# misc.net
KiCad netlist of a schematic drawn in Altium Designer
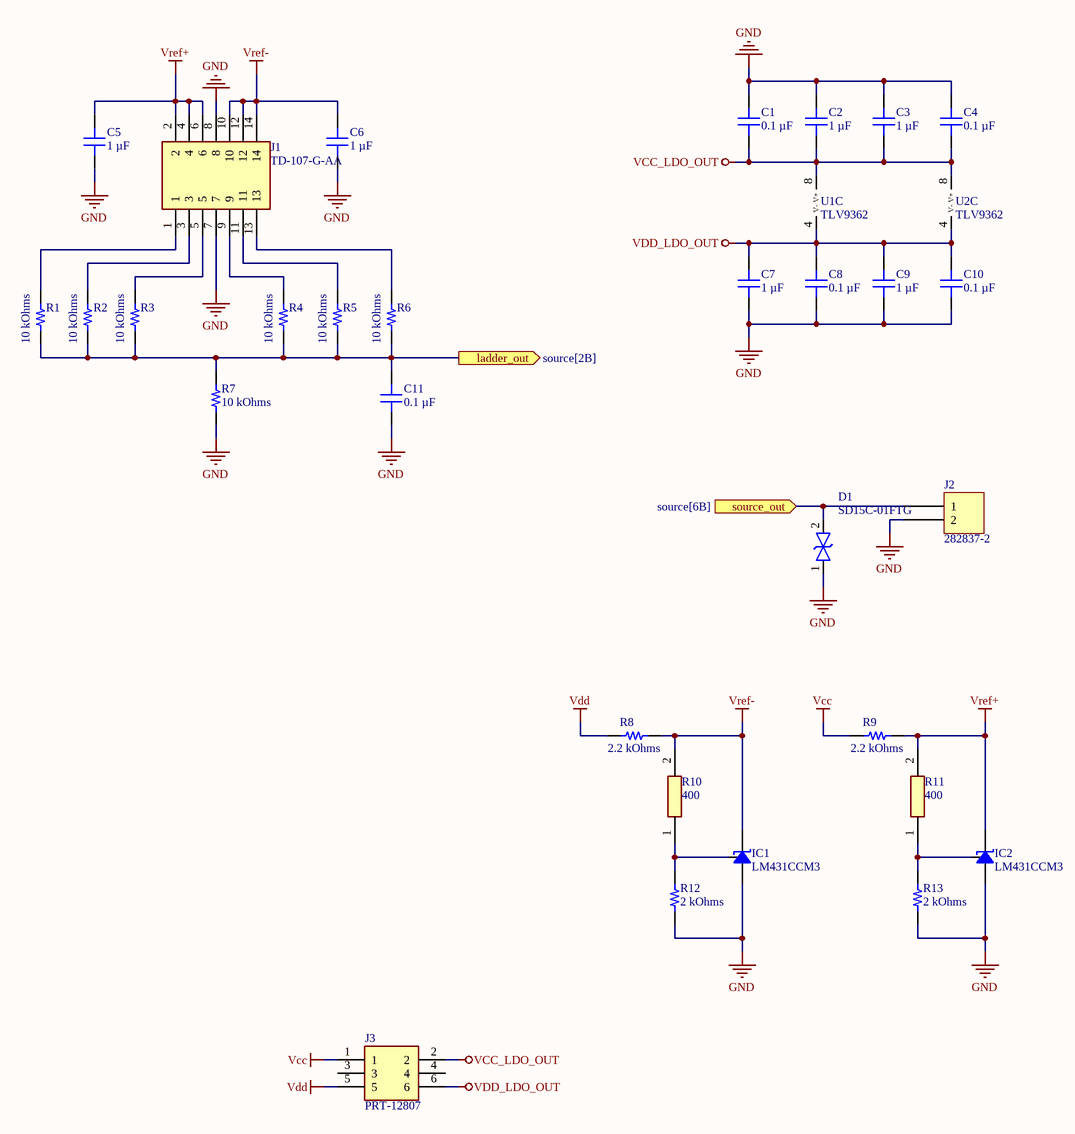
[diagram p0: misc.SchDoc]

(export (version "E")
  (design (tool "Eeschema 10.0.6"))
  (components
    (comp (ref "C1")
      (value "0.1 µF")
      (footprint "CAP 1206_3216 - 0.8MM")
      (description "CAP CER 0.1UF 50V X7R 1206")
      (fields
        (field (name "PART NUMBER") "885012208087")
        (field (name "CAPACITANCE") "0.1 µF")
        (field (name "MANUFACTURER") "Würth Elektronik")
      )
      (libsource (lib "Celestial Altium Library - altium_library") (part "Capacitor"))
    )
    (comp (ref "C2")
      (value "1 µF")
      (footprint "CAP 1206_3216 - 0.8MM")
      (description "CAP CER 1UF 50V X7R 1206")
      (fields
        (field (name "PART NUMBER") "885012208093")
        (field (name "CAPACITANCE") "1 µF")
        (field (name "MANUFACTURER") "Würth Elektronik")
      )
      (libsource (lib "Celestial Altium Library - altium_library") (part "Capacitor"))
    )
    (comp (ref "C3")
      (value "1 µF")
      (footprint "CAP 1206_3216 - 0.8MM")
      (description "CAP CER 1UF 50V X7R 1206")
      (fields
        (field (name "PART NUMBER") "885012208093")
        (field (name "CAPACITANCE") "1 µF")
        (field (name "MANUFACTURER") "Würth Elektronik")
      )
      (libsource (lib "Celestial Altium Library - altium_library") (part "Capacitor"))
    )
    (comp (ref "C4")
      (value "0.1 µF")
      (footprint "CAP 1206_3216 - 0.8MM")
      (description "CAP CER 0.1UF 50V X7R 1206")
      (fields
        (field (name "PART NUMBER") "885012208087")
        (field (name "CAPACITANCE") "0.1 µF")
        (field (name "MANUFACTURER") "Würth Elektronik")
      )
      (libsource (lib "Celestial Altium Library - altium_library") (part "Capacitor"))
    )
    (comp (ref "C5")
      (value "1 µF")
      (footprint "CAP 1206_3216 - 0.8MM")
      (description "CAP CER 1UF 50V X7R 1206")
      (fields
        (field (name "PART NUMBER") "885012208093")
        (field (name "CAPACITANCE") "1 µF")
        (field (name "MANUFACTURER") "Würth Elektronik")
      )
      (libsource (lib "Celestial Altium Library - altium_library") (part "Capacitor"))
    )
    (comp (ref "C6")
      (value "1 µF")
      (footprint "CAP 1206_3216 - 0.8MM")
      (description "CAP CER 1UF 50V X7R 1206")
      (fields
        (field (name "PART NUMBER") "885012208093")
        (field (name "CAPACITANCE") "1 µF")
        (field (name "MANUFACTURER") "Würth Elektronik")
      )
      (libsource (lib "Celestial Altium Library - altium_library") (part "Capacitor"))
    )
    (comp (ref "C7")
      (value "1 µF")
      (footprint "CAP 1206_3216 - 0.8MM")
      (description "CAP CER 1UF 50V X7R 1206")
      (fields
        (field (name "PART NUMBER") "885012208093")
        (field (name "CAPACITANCE") "1 µF")
        (field (name "MANUFACTURER") "Würth Elektronik")
      )
      (libsource (lib "Celestial Altium Library - altium_library") (part "Capacitor"))
    )
    (comp (ref "C8")
      (value "0.1 µF")
      (footprint "CAP 1206_3216 - 0.8MM")
      (description "CAP CER 0.1UF 50V X7R 1206")
      (fields
        (field (name "PART NUMBER") "885012208087")
        (field (name "CAPACITANCE") "0.1 µF")
        (field (name "MANUFACTURER") "Würth Elektronik")
      )
      (libsource (lib "Celestial Altium Library - altium_library") (part "Capacitor"))
    )
    (comp (ref "C9")
      (value "1 µF")
      (footprint "CAP 1206_3216 - 0.8MM")
      (description "CAP CER 1UF 50V X7R 1206")
      (fields
        (field (name "PART NUMBER") "885012208093")
        (field (name "CAPACITANCE") "1 µF")
        (field (name "MANUFACTURER") "Würth Elektronik")
      )
      (libsource (lib "Celestial Altium Library - altium_library") (part "Capacitor"))
    )
    (comp (ref "C10")
      (value "0.1 µF")
      (footprint "CAP 1206_3216 - 0.8MM")
      (description "CAP CER 0.1UF 50V X7R 1206")
      (fields
        (field (name "PART NUMBER") "885012208087")
        (field (name "CAPACITANCE") "0.1 µF")
        (field (name "MANUFACTURER") "Würth Elektronik")
      )
      (libsource (lib "Celestial Altium Library - altium_library") (part "Capacitor"))
    )
    (comp (ref "C11")
      (value "0.1 µF")
      (footprint "CAP 1206_3216 - 0.8MM")
      (description "CAP CER 0.1UF 50V X7R 1206")
      (fields
        (field (name "PART NUMBER") "885012208087")
        (field (name "CAPACITANCE") "0.1 µF")
        (field (name "MANUFACTURER") "Würth Elektronik")
      )
      (libsource (lib "Celestial Altium Library - altium_library") (part "Capacitor"))
    )
    (comp (ref "D1")
      (value "SD15C-01FTG")
      (footprint "za_koncar:SD15C01FTG")
      (description "TVS Diode (Bi-directional)")
      (fields (field (name "MOUSER PART NUMBER") "576-SD15C-01FTG"))
      (libsource (lib "za_koncar") (part "SD15C-01FTG"))
    )
    (comp (ref "IC1")
      (value "LM431CCM3")
      (footprint "SOT96P240X110-3N")
      (description "Integrated Circuit")
      (fields
        (field (name "MANUFACTURER_PART_NUMBER") "LM431CCM3/NOPB")
        (field (name "MOUSER PART NUMBER") "926-LM431CCM3/NOPB")
      )
      (libsource (lib "za_koncar") (part "LM431CCM3_NOPB"))
    )
    (comp (ref "IC2")
      (value "LM431CCM3")
      (footprint "SOT96P240X110-3N")
      (description "Integrated Circuit")
      (fields
        (field (name "MANUFACTURER_PART_NUMBER") "LM431CCM3/NOPB")
        (field (name "MOUSER PART NUMBER") "926-LM431CCM3/NOPB")
      )
      (libsource (lib "za_koncar") (part "LM431CCM3_NOPB"))
    )
    (comp (ref "J1")
      (value "TD-107-G-AA")
      (footprint "HDRV14W46P254_2X7_1778X508X818P")
      (description "Connector")
      (fields (field (name "MOUSER PART NUMBER") "200-TD107GAA"))
      (libsource (lib "za_koncar") (part "TD-107-G-AA"))
    )
    (comp (ref "J2")
      (value "282837-2")
      (footprint "TE 282837-2")
      (description "TERM BLK 2P SIDE ENT 5.08MM PCB")
      (fields (field (name "MANUFACTURER") "TE Connectivity AMP Connectors") (field (name "VOLTAGE") "300 V"))
      (libsource (lib "Celestial Altium Library - altium_library") (part "2 Pin"))
    )
    (comp (ref "J3")
      (value "PRT-12807")
      (footprint "HDRV6W82P254_2X3_762X500X884P")
      (description "Connector")
      (fields (field (name "MOUSER PART NUMBER") "474-PRT-12807"))
      (libsource (lib "za_koncar") (part "PRT-12807"))
    )
    (comp (ref "R1")
      (value "10 kOhms")
      (footprint "YAGEO RES 1206_3216")
      (description "RES SMD 10K OHM 1% 1/4W 1206")
      (fields (field (name "PART NUMBER") "RT1206FRE0710KL") (field (name "MANUFACTURER") "Yageo"))
      (libsource (lib "Celestial Altium Library - altium_library") (part "Resistor"))
    )
    (comp (ref "R2")
      (value "10 kOhms")
      (footprint "YAGEO RES 1206_3216")
      (description "RES SMD 10K OHM 1% 1/4W 1206")
      (fields (field (name "PART NUMBER") "RT1206FRE0710KL") (field (name "MANUFACTURER") "Yageo"))
      (libsource (lib "Celestial Altium Library - altium_library") (part "Resistor"))
    )
    (comp (ref "R3")
      (value "10 kOhms")
      (footprint "YAGEO RES 1206_3216")
      (description "RES SMD 10K OHM 1% 1/4W 1206")
      (fields (field (name "PART NUMBER") "RT1206FRE0710KL") (field (name "MANUFACTURER") "Yageo"))
      (libsource (lib "Celestial Altium Library - altium_library") (part "Resistor"))
    )
    (comp (ref "R4")
      (value "10 kOhms")
      (footprint "YAGEO RES 1206_3216")
      (description "RES SMD 10K OHM 1% 1/4W 1206")
      (fields (field (name "PART NUMBER") "RT1206FRE0710KL") (field (name "MANUFACTURER") "Yageo"))
      (libsource (lib "Celestial Altium Library - altium_library") (part "Resistor"))
    )
    (comp (ref "R5")
      (value "10 kOhms")
      (footprint "YAGEO RES 1206_3216")
      (description "RES SMD 10K OHM 1% 1/4W 1206")
      (fields (field (name "PART NUMBER") "RT1206FRE0710KL") (field (name "MANUFACTURER") "Yageo"))
      (libsource (lib "Celestial Altium Library - altium_library") (part "Resistor"))
    )
    (comp (ref "R6")
      (value "10 kOhms")
      (footprint "YAGEO RES 1206_3216")
      (description "RES SMD 10K OHM 1% 1/4W 1206")
      (fields (field (name "PART NUMBER") "RT1206FRE0710KL") (field (name "MANUFACTURER") "Yageo"))
      (libsource (lib "Celestial Altium Library - altium_library") (part "Resistor"))
    )
    (comp (ref "R7")
      (value "10 kOhms")
      (footprint "YAGEO RES 1206_3216")
      (description "RES SMD 10K OHM 1% 1/4W 1206")
      (fields (field (name "PART NUMBER") "RT1206FRE0710KL") (field (name "MANUFACTURER") "Yageo"))
      (libsource (lib "Celestial Altium Library - altium_library") (part "Resistor"))
    )
    (comp (ref "R8")
      (value "2.2 kOhms")
      (footprint "RES 1206_3216")
      (description "RES SMD 2.2K OHM 5% 1/4W 1206")
      (fields
        (field (name "PART NUMBER") "ERJ-8GEYJ222V")
        (field (name "MANUFACTURER") "Panasonic Electronic Components")
      )
      (libsource (lib "Celestial Altium Library - altium_library") (part "Resistor"))
    )
    (comp (ref "R9")
      (value "2.2 kOhms")
      (footprint "RES 1206_3216")
      (description "RES SMD 2.2K OHM 5% 1/4W 1206")
      (fields
        (field (name "PART NUMBER") "ERJ-8GEYJ222V")
        (field (name "MANUFACTURER") "Panasonic Electronic Components")
      )
      (libsource (lib "Celestial Altium Library - altium_library") (part "Resistor"))
    )
    (comp (ref "R10")
      (value "400")
      (footprint "RESC3116X65N")
      (description "Resistor")
      (fields
        (field (name "MANUFACTURER_PART_NUMBER") "RT1206BRD07400RL")
        (field (name "MOUSER PART NUMBER") "603-RT1206BRD07400RL")
      )
      (libsource (lib "za_koncar") (part "RT1206BRD07400RL"))
    )
    (comp (ref "R11")
      (value "400")
      (footprint "RESC3116X65N")
      (description "Resistor")
      (fields
        (field (name "MANUFACTURER_PART_NUMBER") "RT1206BRD07400RL")
        (field (name "MOUSER PART NUMBER") "603-RT1206BRD07400RL")
      )
      (libsource (lib "za_koncar") (part "RT1206BRD07400RL"))
    )
    (comp (ref "R12")
      (value "2 kOhms")
      (footprint "RES 1206_3216")
      (description "RES SMD 2K OHM 0.1% 1/4W 1206")
      (fields
        (field (name "PART NUMBER") "ERA-8AEB202V")
        (field (name "MANUFACTURER") "Panasonic Electronic Components")
      )
      (libsource (lib "Celestial Altium Library - altium_library") (part "Resistor"))
    )
    (comp (ref "R13")
      (value "2 kOhms")
      (footprint "RES 1206_3216")
      (description "RES SMD 2K OHM 0.1% 1/4W 1206")
      (fields
        (field (name "PART NUMBER") "ERA-8AEB202V")
        (field (name "MANUFACTURER") "Panasonic Electronic Components")
      )
      (libsource (lib "Celestial Altium Library - altium_library") (part "Resistor"))
    )
    (comp (ref "U1")
      (value "TLV9362")
      (footprint "SOIC8-127P600X175-8N")
      (description "TLV936x 10-MHz, 40-V, RRO, Operational Amplifie")
      (libsource (lib "za_koncar") (part "TLV9362"))
    )
    (comp (ref "U2")
      (value "TLV9362")
      (footprint "SOIC8-127P600X175-8N")
      (description "TLV936x 10-MHz, 40-V, RRO, Operational Amplifie")
      (libsource (lib "za_koncar") (part "TLV9362"))
    )
  )
  (nets
    (net (code "1") (name "/ladder_out") (class "Default")
      (node (ref "C11") (pin "1") (pinfunction "1_1") (pintype "passive"))
      (node (ref "R1") (pin "1") (pinfunction "1_1") (pintype "passive"))
      (node (ref "R2") (pin "1") (pinfunction "1_1") (pintype "passive"))
      (node (ref "R3") (pin "1") (pinfunction "1_1") (pintype "passive"))
      (node (ref "R4") (pin "1") (pinfunction "1_1") (pintype "passive"))
      (node (ref "R5") (pin "1") (pinfunction "1_1") (pintype "passive"))
      (node (ref "R6") (pin "1") (pinfunction "1_1") (pintype "passive"))
      (node (ref "R7") (pin "2") (pinfunction "2_2") (pintype "passive"))
    )
    (net (code "2") (name "/source_out") (class "Default")
      (node (ref "D1") (pin "2") (pinfunction "2_2") (pintype "passive"))
      (node (ref "J2") (pin "1") (pinfunction "1_1") (pintype "passive"))
    )
    (net (code "3") (name "GND") (class "Default")
      (node (ref "C1") (pin "1") (pinfunction "1_1") (pintype "passive"))
      (node (ref "C10") (pin "2") (pinfunction "2_2") (pintype "passive"))
      (node (ref "C11") (pin "2") (pinfunction "2_2") (pintype "passive"))
      (node (ref "C2") (pin "1") (pinfunction "1_1") (pintype "passive"))
      (node (ref "C3") (pin "2") (pinfunction "2_2") (pintype "passive"))
      (node (ref "C4") (pin "2") (pinfunction "2_2") (pintype "passive"))
      (node (ref "C5") (pin "2") (pinfunction "2_2") (pintype "passive"))
      (node (ref "C6") (pin "1") (pinfunction "1_1") (pintype "passive"))
      (node (ref "C7") (pin "2") (pinfunction "2_2") (pintype "passive"))
      (node (ref "C8") (pin "2") (pinfunction "2_2") (pintype "passive"))
      (node (ref "C9") (pin "2") (pinfunction "2_2") (pintype "passive"))
      (node (ref "D1") (pin "1") (pinfunction "1_1") (pintype "passive"))
      (node (ref "IC1") (pin "2") (pinfunction "Anode_2") (pintype "passive"))
      (node (ref "IC2") (pin "2") (pinfunction "Anode_2") (pintype "passive"))
      (node (ref "J1") (pin "7") (pinfunction "7_7") (pintype "passive"))
      (node (ref "J1") (pin "8") (pinfunction "8_8") (pintype "passive"))
      (node (ref "J2") (pin "2") (pinfunction "2_2") (pintype "passive"))
      (node (ref "R12") (pin "1") (pinfunction "1_1") (pintype "passive"))
      (node (ref "R13") (pin "1") (pinfunction "1_1") (pintype "passive"))
      (node (ref "R7") (pin "1") (pinfunction "1_1") (pintype "passive"))
    )
    (net (code "4") (name "Net-(IC1-Ref)") (class "Default")
      (node (ref "IC1") (pin "3") (pinfunction "Ref_3") (pintype "passive"))
      (node (ref "R10") (pin "1") (pinfunction "1_1") (pintype "passive"))
      (node (ref "R12") (pin "2") (pinfunction "2_2") (pintype "passive"))
    )
    (net (code "5") (name "Net-(IC2-Ref)") (class "Default")
      (node (ref "IC2") (pin "3") (pinfunction "Ref_3") (pintype "passive"))
      (node (ref "R11") (pin "1") (pinfunction "1_1") (pintype "passive"))
      (node (ref "R13") (pin "2") (pinfunction "2_2") (pintype "passive"))
    )
    (net (code "6") (name "Net-(J1-Pad1)") (class "Default")
      (node (ref "J1") (pin "1") (pinfunction "1_1") (pintype "passive"))
      (node (ref "R1") (pin "2") (pinfunction "2_2") (pintype "passive"))
    )
    (net (code "7") (name "Net-(J1-Pad3)") (class "Default")
      (node (ref "J1") (pin "3") (pinfunction "3_3") (pintype "passive"))
      (node (ref "R2") (pin "2") (pinfunction "2_2") (pintype "passive"))
    )
    (net (code "8") (name "Net-(J1-Pad5)") (class "Default")
      (node (ref "J1") (pin "5") (pinfunction "5_5") (pintype "passive"))
      (node (ref "R3") (pin "2") (pinfunction "2_2") (pintype "passive"))
    )
    (net (code "9") (name "Net-(J1-Pad9)") (class "Default")
      (node (ref "J1") (pin "9") (pinfunction "9_9") (pintype "passive"))
      (node (ref "R4") (pin "2") (pinfunction "2_2") (pintype "passive"))
    )
    (net (code "10") (name "Net-(J1-Pad11)") (class "Default")
      (node (ref "J1") (pin "11") (pinfunction "11_11") (pintype "passive"))
      (node (ref "R5") (pin "2") (pinfunction "2_2") (pintype "passive"))
    )
    (net (code "11") (name "Net-(J1-Pad13)") (class "Default")
      (node (ref "J1") (pin "13") (pinfunction "13_13") (pintype "passive"))
      (node (ref "R6") (pin "2") (pinfunction "2_2") (pintype "passive"))
    )
    (net (code "12") (name "VCC_LDO_OUT") (class "Default")
      (node (ref "C1") (pin "2") (pinfunction "2_2") (pintype "passive"))
      (node (ref "C2") (pin "2") (pinfunction "2_2") (pintype "passive"))
      (node (ref "C3") (pin "1") (pinfunction "1_1") (pintype "passive"))
      (node (ref "C4") (pin "1") (pinfunction "1_1") (pintype "passive"))
      (node (ref "J3") (pin "2") (pinfunction "2_2") (pintype "passive"))
      (node (ref "U1") (pin "8") (pinfunction "V+_8") (pintype "power_in"))
      (node (ref "U2") (pin "8") (pinfunction "V+_8") (pintype "power_in"))
    )
    (net (code "13") (name "VDD_LDO_OUT") (class "Default")
      (node (ref "C10") (pin "1") (pinfunction "1_1") (pintype "passive"))
      (node (ref "C7") (pin "1") (pinfunction "1_1") (pintype "passive"))
      (node (ref "C8") (pin "1") (pinfunction "1_1") (pintype "passive"))
      (node (ref "C9") (pin "1") (pinfunction "1_1") (pintype "passive"))
      (node (ref "J3") (pin "6") (pinfunction "6_6") (pintype "passive"))
      (node (ref "U1") (pin "4") (pinfunction "V-_4") (pintype "power_in"))
      (node (ref "U2") (pin "4") (pinfunction "V-_4") (pintype "power_in"))
    )
    (net (code "14") (name "Vcc") (class "Default")
      (node (ref "J3") (pin "1") (pinfunction "1_1") (pintype "passive"))
      (node (ref "R9") (pin "1") (pinfunction "1_1") (pintype "passive"))
    )
    (net (code "15") (name "Vdd") (class "Default")
      (node (ref "J3") (pin "5") (pinfunction "5_5") (pintype "passive"))
      (node (ref "R8") (pin "1") (pinfunction "1_1") (pintype "passive"))
    )
    (net (code "16") (name "Vref+") (class "Default")
      (node (ref "C5") (pin "1") (pinfunction "1_1") (pintype "passive"))
      (node (ref "IC2") (pin "1") (pinfunction "Cathode_1") (pintype "passive"))
      (node (ref "J1") (pin "2") (pinfunction "2_2") (pintype "passive"))
      (node (ref "J1") (pin "4") (pinfunction "4_4") (pintype "passive"))
      (node (ref "J1") (pin "6") (pinfunction "6_6") (pintype "passive"))
      (node (ref "R11") (pin "2") (pinfunction "2_2") (pintype "passive"))
      (node (ref "R9") (pin "2") (pinfunction "2_2") (pintype "passive"))
    )
    (net (code "17") (name "Vref-") (class "Default")
      (node (ref "C6") (pin "2") (pinfunction "2_2") (pintype "passive"))
      (node (ref "IC1") (pin "1") (pinfunction "Cathode_1") (pintype "passive"))
      (node (ref "J1") (pin "10") (pinfunction "10_10") (pintype "passive"))
      (node (ref "J1") (pin "12") (pinfunction "12_12") (pintype "passive"))
      (node (ref "J1") (pin "14") (pinfunction "14_14") (pintype "passive"))
      (node (ref "R10") (pin "2") (pinfunction "2_2") (pintype "passive"))
      (node (ref "R8") (pin "2") (pinfunction "2_2") (pintype "passive"))
    )
    (net (code "18") (name "unconnected-(J3-Pad3)") (class "Default")
      (node (ref "J3") (pin "3") (pinfunction "3_3") (pintype "passive"))
    )
    (net (code "19") (name "unconnected-(J3-Pad4)") (class "Default")
      (node (ref "J3") (pin "4") (pinfunction "4_4") (pintype "passive"))
    )
  )
)
